# Power_Sergeant.net
KiCad netlist of a schematic drawn in Altium Designer
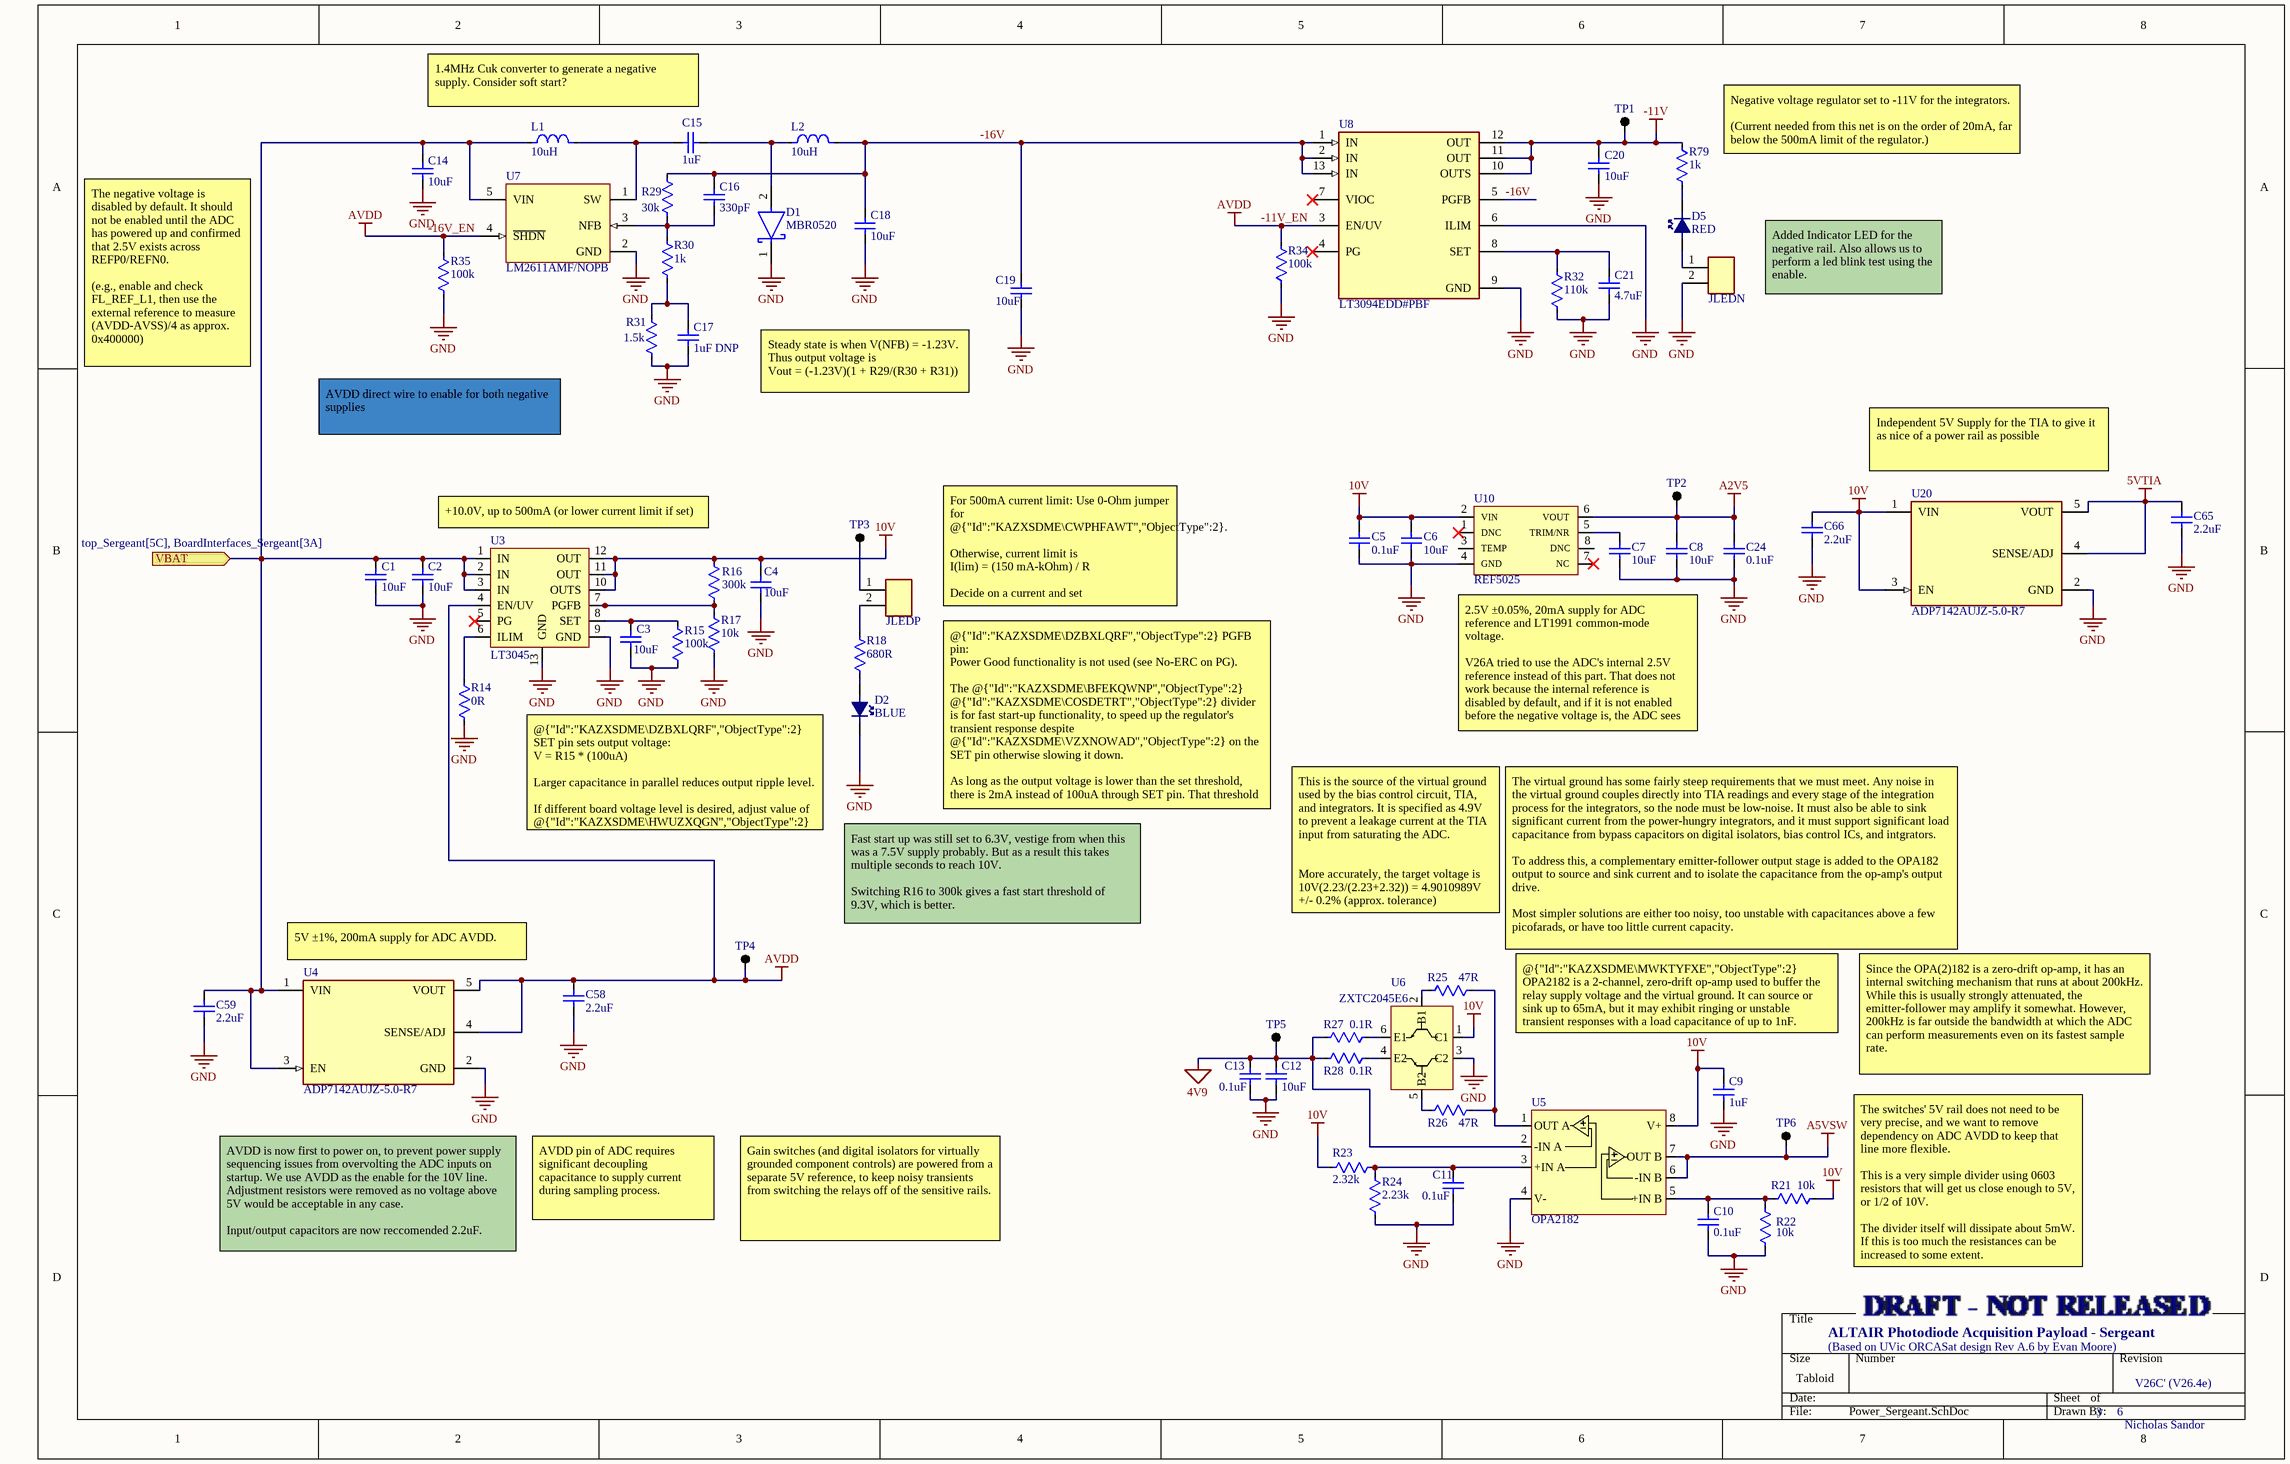
[diagram p0: Power_Sergeant.SchDoc]

(export (version "E")
  (design (tool "Eeschema 10.0.6"))
  (components
    (comp (ref "C1")
      (value "10uF")
      (footprint "CAP 1206 IPC LOW DENSITY")
      (description "Murata GRT319R6YA106KE01D - Cap Ceramic 10uF 35V X5R 10% Pad SMD 1206 85C Automotive T/R")
      (fields (field (name "MF") "Murata") (field (name "MP") "GRT319R6YA106KE01D"))
      (libsource (lib "ALTAIR_PD_Capacitors") (part "CAP"))
    )
    (comp (ref "C2")
      (value "10uF")
      (footprint "CAP 1206 IPC LOW DENSITY")
      (description "Murata GRT319R6YA106KE01D - Cap Ceramic 10uF 35V X5R 10% Pad SMD 1206 85C Automotive T/R")
      (fields (field (name "MF") "Murata") (field (name "MP") "GRT319R6YA106KE01D"))
      (libsource (lib "ALTAIR_PD_Capacitors") (part "CAP"))
    )
    (comp (ref "C3")
      (value "10uF")
      (footprint "CAP 1206 IPC LOW DENSITY")
      (description "Murata GRT319R6YA106KE01D - Cap Ceramic 10uF 35V X5R 10% Pad SMD 1206 85C Automotive T/R")
      (fields (field (name "MF") "Murata") (field (name "MP") "GRT319R6YA106KE01D"))
      (libsource (lib "ALTAIR_PD_Capacitors") (part "CAP"))
    )
    (comp (ref "C4")
      (value "10uF")
      (footprint "CAP 1206 IPC LOW DENSITY")
      (description "Murata GRT319R6YA106KE01D - Cap Ceramic 10uF 35V X5R 10% Pad SMD 1206 85C Automotive T/R")
      (fields (field (name "MF") "Murata") (field (name "MP") "GRT319R6YA106KE01D"))
      (libsource (lib "ALTAIR_PD_Capacitors") (part "CAP"))
    )
    (comp (ref "C5")
      (value "0.1uF")
      (footprint "CAP 0603 IPC MID DENSITY")
      (description "Kemet C0603C104K5RACAUTO - Cap Ceramic 0.1uF 50V X7R 10% 0603 125C Paper T/R")
      (fields (field (name "MF") "Kemet") (field (name "MP") "C0603C104K5RACAUTO"))
      (libsource (lib "ALTAIR_PD_Capacitors") (part "CAP"))
    )
    (comp (ref "C6")
      (value "10uF")
      (footprint "CAP 0805 IPC MID DENSITY")
      (description "Murata GRM21BR61E106KA73L - Cap Ceramic 10uF 10% 25V X5R 0805")
      (fields (field (name "MF") "Murata") (field (name "MP") "GRM21BR61E106KA73L"))
      (libsource (lib "ALTAIR_PD_Capacitors") (part "CAP"))
    )
    (comp (ref "C7")
      (value "10uF")
      (footprint "CAP 0805 IPC MID DENSITY")
      (description "Murata GRM21BR61E106KA73L - Cap Ceramic 10uF 10% 25V X5R 0805")
      (fields (field (name "MF") "Murata") (field (name "MP") "GRM21BR61E106KA73L"))
      (libsource (lib "ALTAIR_PD_Capacitors") (part "CAP"))
    )
    (comp (ref "C8")
      (value "10uF")
      (footprint "CAP 0805 IPC MID DENSITY")
      (description "Murata GRM21BR61E106KA73L - Cap Ceramic 10uF 10% 25V X5R 0805")
      (fields (field (name "MF") "Murata") (field (name "MP") "GRM21BR61E106KA73L"))
      (libsource (lib "ALTAIR_PD_Capacitors") (part "CAP"))
    )
    (comp (ref "C9")
      (value "1uF")
      (footprint "CAP 0603 IPC MID DENSITY")
      (description "Murata GRT188R61H105KE13D - Cap MLCC AEC-Q200 X5R 1uF 50V 0603")
      (fields (field (name "MF") "Murata") (field (name "MP") "GRT188R61H105KE13D"))
      (libsource (lib "ALTAIR_PD_Capacitors") (part "CAP"))
    )
    (comp (ref "C10")
      (value "0.1uF")
      (footprint "CAP 0603 IPC MID DENSITY")
      (description "Kemet C0603C104K5RACAUTO - Cap Ceramic 0.1uF 50V X7R 10% 0603 125C Paper T/R")
      (fields (field (name "MF") "Kemet") (field (name "MP") "C0603C104K5RACAUTO"))
      (libsource (lib "ALTAIR_PD_Capacitors") (part "CAP"))
    )
    (comp (ref "C11")
      (value "0.1uF")
      (footprint "CAP 0603 IPC MID DENSITY")
      (description "Kemet C0603C104K5RACAUTO - Cap Ceramic 0.1uF 50V X7R 10% 0603 125C Paper T/R")
      (fields (field (name "MF") "Kemet") (field (name "MP") "C0603C104K5RACAUTO"))
      (libsource (lib "ALTAIR_PD_Capacitors") (part "CAP"))
    )
    (comp (ref "C12")
      (value "10uF")
      (footprint "CAP 1206 IPC LOW DENSITY")
      (description "Murata GRT319R6YA106KE01D - Cap Ceramic 10uF 35V X5R 10% Pad SMD 1206 85C Automotive T/R")
      (fields (field (name "MF") "Murata") (field (name "MP") "GRT319R6YA106KE01D"))
      (libsource (lib "ALTAIR_PD_Capacitors") (part "CAP"))
    )
    (comp (ref "C13")
      (value "0.1uF")
      (footprint "CAP 0603 IPC MID DENSITY")
      (description "Kemet C0603C104K5RACAUTO - Cap Ceramic 0.1uF 50V X7R 10% 0603 125C Paper T/R")
      (fields (field (name "MF") "Kemet") (field (name "MP") "C0603C104K5RACAUTO"))
      (libsource (lib "ALTAIR_PD_Capacitors") (part "CAP"))
    )
    (comp (ref "C14")
      (value "10uF")
      (footprint "CAP 0805 IPC MID DENSITY")
      (description "Murata GRM21BR61E106KA73L - Cap Ceramic 10uF 10% 25V X5R 0805")
      (fields (field (name "MF") "Murata") (field (name "MP") "GRM21BR61E106KA73L"))
      (libsource (lib "ALTAIR_PD_Capacitors") (part "CAP"))
    )
    (comp (ref "C15")
      (value "1uF")
      (footprint "CAP 0603 IPC MID DENSITY")
      (description "Murata GRT188R61H105KE13D - Cap MLCC AEC-Q200 X5R 1uF 50V 0603")
      (fields (field (name "MF") "Murata") (field (name "MP") "GRT188R61H105KE13D"))
      (libsource (lib "ALTAIR_PD_Capacitors") (part "CAP"))
    )
    (comp (ref "C16")
      (value "330pF")
      (footprint "CAP 1206 NON-IPC KEMET NP0")
      (description "Kemet C1206C331J5GACTU - Cap Ceramic 330pF 50V 5% NP0 1206")
      (fields (field (name "MF") "Kemet") (field (name "MP") "C1206C331J5GACTU"))
      (libsource (lib "ALTAIR_PD_Capacitors") (part "CAP"))
    )
    (comp (ref "C17")
      (value "1uF DNP")
      (footprint "CAP 0603 IPC MID DENSITY")
      (description "Murata GRT188R61H105KE13D - Cap MLCC AEC-Q200 X5R 1uF 50V 0603")
      (fields (field (name "MF") "Murata") (field (name "MP") "GRT188R61H105KE13D"))
      (libsource (lib "ALTAIR_PD_Capacitors") (part "CAP"))
    )
    (comp (ref "C18")
      (value "10uF")
      (footprint "CAP 0805 IPC MID DENSITY")
      (description "Murata GRM21BR61E106KA73L - Cap Ceramic 10uF 10% 25V X5R 0805")
      (fields (field (name "MF") "Murata") (field (name "MP") "GRM21BR61E106KA73L"))
      (libsource (lib "ALTAIR_PD_Capacitors") (part "CAP"))
    )
    (comp (ref "C19")
      (value "10uF")
      (footprint "CAP 0805 IPC MID DENSITY")
      (description "Murata GRM21BR61E106KA73L - Cap Ceramic 10uF 10% 25V X5R 0805")
      (fields (field (name "MF") "Murata") (field (name "MP") "GRM21BR61E106KA73L"))
      (libsource (lib "ALTAIR_PD_Capacitors") (part "CAP"))
    )
    (comp (ref "C20")
      (value "10uF")
      (footprint "CAP 0805 IPC MID DENSITY")
      (description "Murata GRM21BR61E106KA73L - Cap Ceramic 10uF 10% 25V X5R 0805")
      (fields (field (name "MF") "Murata") (field (name "MP") "GRM21BR61E106KA73L"))
      (libsource (lib "ALTAIR_PD_Capacitors") (part "CAP"))
    )
    (comp (ref "C21")
      (value "4.7uF")
      (footprint "CAP 0805 NON-IPC KEMET X5R")
      (description "Kemet C0805C475K8PACTU - Cap Ceramic 4.7uF 10V X5R 0805")
      (fields (field (name "MF") "Kemet") (field (name "MP") "C0805C475K8PACTU"))
      (libsource (lib "ALTAIR_PD_Capacitors") (part "CAP"))
    )
    (comp (ref "C24")
      (value "0.1uF")
      (footprint "CAP 0603 IPC MID DENSITY")
      (description "Kemet C0603C104K5RACAUTO - Cap Ceramic 0.1uF 50V X7R 10% 0603 125C Paper T/R")
      (fields (field (name "MF") "Kemet") (field (name "MP") "C0603C104K5RACAUTO"))
      (libsource (lib "ALTAIR_PD_Capacitors") (part "CAP"))
    )
    (comp (ref "C58")
      (value "2.2uF")
      (footprint "CAP 1206 UNKNOWN")
      (description "CL31B225KBHNNNE CAP CER 2.2UF 50V X7R 1206")
      (fields (field (name "MF") "Samsung Electro-Mechanics") (field (name "MP") "CL31B225KBHNNNE"))
      (libsource (lib "ALTAIR_PD_Capacitors") (part "CAP"))
    )
    (comp (ref "C59")
      (value "2.2uF")
      (footprint "CAP 1206 UNKNOWN")
      (description "CL31B225KBHNNNE CAP CER 2.2UF 50V X7R 1206")
      (fields (field (name "MF") "Samsung Electro-Mechanics") (field (name "MP") "CL31B225KBHNNNE"))
      (libsource (lib "ALTAIR_PD_Capacitors") (part "CAP"))
    )
    (comp (ref "C65")
      (value "2.2uF")
      (footprint "CAP 1206 UNKNOWN")
      (description "CL31B225KBHNNNE CAP CER 2.2UF 50V X7R 1206")
      (fields (field (name "MF") "Samsung Electro-Mechanics") (field (name "MP") "CL31B225KBHNNNE"))
      (libsource (lib "ALTAIR_PD_Capacitors") (part "CAP"))
    )
    (comp (ref "C66")
      (value "2.2uF")
      (footprint "CAP 1206 UNKNOWN")
      (description "CL31B225KBHNNNE CAP CER 2.2UF 50V X7R 1206")
      (fields (field (name "MF") "Samsung Electro-Mechanics") (field (name "MP") "CL31B225KBHNNNE"))
      (libsource (lib "ALTAIR_PD_Capacitors") (part "CAP"))
    )
    (comp (ref "D1")
      (value "MBR0520")
      (footprint "SOD-123 ONSEMI SMALL PADS")
      (description "DIODE SCHOTTKY 20V 500MA SOD123")
      (fields (field (name "MF") "onsemi") (field (name "MP") "MBR0520LT1G"))
      (libsource (lib "ALTAIR_PD_Diodes") (part "Schottky"))
    )
    (comp (ref "D2")
      (value "BLUE")
      (footprint "LED 0603 MID DENSITY")
      (description "LED BLUE CLEAR 0603 SMD")
      (fields (field (name "MF") "Wurth Electronics") (field (name "MP") "150060BS75000"))
      (libsource (lib "ALTAIR_PD_Diodes") (part "LED-blue"))
    )
    (comp (ref "D5")
      (value "RED")
      (footprint "LED 0603 MID DENSITY")
      (description "LED RED CLEAR 0603 SMD")
      (fields (field (name "MF") "Wurth Electronics") (field (name "MP") "150060RS75000"))
      (libsource (lib "ALTAIR_PD_Diodes") (part "LED-blue"))
    )
    (comp (ref "JLEDN")
      (value "JLED")
      (footprint "JUMPER 2POS 1MM PITCH THT")
      (description "2x1 Header THT 1mm Pitch")
      (fields
        (field (name "MF") "GCT (GLOBAL CONNECTOR TECHNOLOGY)")
        (field (name "MP") "BC020-02-A-0200-0300-L-G")
      )
      (libsource (lib "ALTAIR_PD_Headers") (part "BC020-02-A-0200-0300-L-G"))
    )
    (comp (ref "JLEDP")
      (value "JLED")
      (footprint "ALTAIR_PD_Headers:JUMPER 2POS 1MM PITCH THT")
      (description "2x1 Header THT 1mm Pitch")
      (fields
        (field (name "MF") "GCT (GLOBAL CONNECTOR TECHNOLOGY)")
        (field (name "MP") "BC020-02-A-0200-0300-L-G")
      )
      (libsource (lib "ALTAIR_PD_Headers") (part "BC020-02-A-0200-0300-L-G"))
    )
    (comp (ref "L1")
      (value "10uH")
      (footprint "IND VLS3012CX-1 NONSTANDARD TDK")
      (description "TDK VLS3012CX-100M-1 - Inductor 10uH 20% 1.25A 0.324Ohm NonstandardPkg")
      (fields (field (name "TOLERANCE") "20%") (field (name "MF") "TDK Corporation"))
      (libsource (lib "ALTAIR_PD_Inductors") (part "IND"))
    )
    (comp (ref "L2")
      (value "10uH")
      (footprint "IND VLS3012CX-1 NONSTANDARD TDK")
      (description "TDK VLS3012CX-100M-1 - Inductor 10uH 20% 1.25A 0.324Ohm NonstandardPkg")
      (fields (field (name "TOLERANCE") "20%") (field (name "MF") "TDK Corporation"))
      (libsource (lib "ALTAIR_PD_Inductors") (part "IND"))
    )
    (comp (ref "R14")
      (value "0R")
      (footprint "RES 0603 IPC MID DENSITY")
      (description "Vishay CRCW06030000Z0EA - Res 0 Ohms 1/8W SMD 0603")
      (fields (field (name "MF") "Vishay Dale") (field (name "MP") "CRCW06030000Z0EA"))
      (libsource (lib "ALTAIR_PD_Resistors") (part "RES"))
    )
    (comp (ref "R15")
      (value "100k")
      (footprint "RES 0603 IPC MID DENSITY")
      (description "Panasonic ERA-3ARB104V - Res SMD 0603 0.1% 0.10W T.C. 10ppm 100K")
      (fields (field (name "MF") "Panasonic Electronic Components") (field (name "MP") "ERA-3ARB104V"))
      (libsource (lib "ALTAIR_PD_Resistors") (part "RES"))
    )
    (comp (ref "R16")
      (value "300k")
      (footprint "RES 0603 IPC MID DENSITY")
      (description "Vishay MCT06030C3003FP500 - Res SMD 300kOhm 1% 1/10W 0603")
      (fields (field (name "MF") "Vishay Dale") (field (name "MP") "MCT06030C3003FP500"))
      (libsource (lib "ALTAIR_PD_Resistors") (part "RES"))
    )
    (comp (ref "R17")
      (value "10k")
      (footprint "RES 0603 IPC MID DENSITY")
      (description "Vishay CRCW060310K0FKEA SMD 0603 10k, CRCW e3 Series, 75V, thick film, 100mW")
      (fields (field (name "MF") "Vishay Dale") (field (name "MP") "CRCW060310K0FKEA"))
      (libsource (lib "ALTAIR_PD_Resistors") (part "RES"))
    )
    (comp (ref "R18")
      (value "680R")
      (footprint "RES 0603 IPC MID DENSITY")
      (description "Panasonic ERJ-3EKF6800V - Res SMD 680 Ohm 1% 1/10W 0603")
      (fields (field (name "MF") "Panasonic Electronic Components") (field (name "MP") "ERJ-3EKF6800V"))
      (libsource (lib "ALTAIR_PD_Resistors") (part "RES"))
    )
    (comp (ref "R21")
      (value "10k")
      (footprint "RES 0603 IPC MID DENSITY")
      (description "Vishay CRCW060310K0FKEA SMD 0603 10k, CRCW e3 Series, 75V, thick film, 100mW")
      (fields (field (name "MF") "Vishay Dale") (field (name "MP") "CRCW060310K0FKEA"))
      (libsource (lib "ALTAIR_PD_Resistors") (part "RES"))
    )
    (comp (ref "R22")
      (value "10k")
      (footprint "RES 0603 IPC MID DENSITY")
      (description "Vishay CRCW060310K0FKEA SMD 0603 10k, CRCW e3 Series, 75V, thick film, 100mW")
      (fields (field (name "MF") "Vishay Dale") (field (name "MP") "CRCW060310K0FKEA"))
      (libsource (lib "ALTAIR_PD_Resistors") (part "RES"))
    )
    (comp (ref "R23")
      (value "2.32k")
      (footprint "RES 0603 IPC MID DENSITY")
      (description "Vishay TNPW06032K32BEEA - Res 2.32k 0.1% 0.21W SMD 0603")
      (fields (field (name "MF") "Vishay Dale") (field (name "MP") "TNPW06032K32BEEA"))
      (libsource (lib "ALTAIR_PD_Resistors") (part "RES"))
    )
    (comp (ref "R24")
      (value "2.23k")
      (footprint "RES 0603 IPC MID DENSITY")
      (description "KOA Speer RN73R1JTTD2231B25 - Res 2.23k 0.1% 1/10W SMD 0603")
      (fields (field (name "MF") "KOA Speer Electronics, Inc.") (field (name "MP") "RN73R1JTTD2231B25"))
      (libsource (lib "ALTAIR_PD_Resistors") (part "RES"))
    )
    (comp (ref "R25")
      (value "47R")
      (footprint "RES 0402 NON-IPC SEI")
      (description "Stackpole RMCF0402JT47R0 - Res 47Ohm 5% 0.063W 0402 Thick Film AEC-Q200 compliant")
      (fields (field (name "MF") "Stackpole Electronics Inc.") (field (name "MP") "RMCF0402JT47R0"))
      (libsource (lib "ALTAIR_PD_Resistors") (part "RES"))
    )
    (comp (ref "R26")
      (value "47R")
      (footprint "RES 0402 NON-IPC SEI")
      (description "Stackpole RMCF0402JT47R0 - Res 47Ohm 5% 0.063W 0402 Thick Film AEC-Q200 compliant")
      (fields (field (name "MF") "Stackpole Electronics Inc.") (field (name "MP") "RMCF0402JT47R0"))
      (libsource (lib "ALTAIR_PD_Resistors") (part "RES"))
    )
    (comp (ref "R27")
      (value "0.1R")
      (footprint "RES 0402 NON-IPC YAGEO")
      (description "Yageo RL0402JR-070R1L - Res 0.1Ohm 5% 1/16W SMD 0402")
      (fields (field (name "MF") "YAGEO") (field (name "MP") "RL0402JR-070R1L"))
      (libsource (lib "ALTAIR_PD_Resistors") (part "RES"))
    )
    (comp (ref "R28")
      (value "0.1R")
      (footprint "RES 0402 NON-IPC YAGEO")
      (description "Yageo RL0402JR-070R1L - Res 0.1Ohm 5% 1/16W SMD 0402")
      (fields (field (name "MF") "YAGEO") (field (name "MP") "RL0402JR-070R1L"))
      (libsource (lib "ALTAIR_PD_Resistors") (part "RES"))
    )
    (comp (ref "R29")
      (value "30k")
      (footprint "RES 0805 IPC HIGH DENSITY")
      (description "Panasonic ERA-6AEB303V - Res 30kOhm 0.1% 1/8W 0805")
      (fields (field (name "MF") "Panasonic Electronic Components") (field (name "MP") "ERA-6AEB303V"))
      (libsource (lib "ALTAIR_PD_Resistors") (part "RES"))
    )
    (comp (ref "R30")
      (value "1k")
      (footprint "RES 0402 IPC LOW DENSITY YAGEO")
      (description "Yageo RC0402FR-071KL - Res 1kOhm 1% 1/16W 0402")
      (fields (field (name "MF") "YAGEO") (field (name "MP") "RC0402FR-071KL"))
      (libsource (lib "ALTAIR_PD_Resistors") (part "RES"))
    )
    (comp (ref "R31")
      (value "1.5k")
      (footprint "RES 1206 NON-IPC VISHAY")
      (description "Vishay TNPU12061K50BZEN00 - Res 1.5kOhm 0.1% 1/4W 1206")
      (fields (field (name "MF") "Vishay Dale") (field (name "MP") "TNPU12061K50BZEN00"))
      (libsource (lib "ALTAIR_PD_Resistors") (part "RES"))
    )
    (comp (ref "R32")
      (value "110k")
      (footprint "RES 0603 IPC MID DENSITY")
      (description "Panasonic ERA-3AEB114V - Res 110k 0.1% 1/10W SMD 0603")
      (fields (field (name "MF") "Panasonic Electronic Components") (field (name "MP") "ERA-3AEB114V"))
      (libsource (lib "ALTAIR_PD_Resistors") (part "RES"))
    )
    (comp (ref "R34")
      (value "100k")
      (footprint "RES 0603 IPC MID DENSITY")
      (description "Panasonic ERJ-3GEYJ104V - Res 100k 5% 1/10W SMD 0603")
      (fields (field (name "MF") "Panasonic Electronic Components") (field (name "MP") "ERJ-3GEYJ104V"))
      (libsource (lib "ALTAIR_PD_Resistors") (part "RES"))
    )
    (comp (ref "R35")
      (value "100k")
      (footprint "RES 0603 IPC MID DENSITY")
      (description "Panasonic ERJ-3GEYJ104V - Res 100k 5% 1/10W SMD 0603")
      (fields (field (name "MF") "Panasonic Electronic Components") (field (name "MP") "ERJ-3GEYJ104V"))
      (libsource (lib "ALTAIR_PD_Resistors") (part "RES"))
    )
    (comp (ref "R79")
      (value "1k")
      (footprint "RES 0603 IPC MID DENSITY")
      (description "Panasonic ERJ-U03F1001V - Res SMD 1 kOhm 1% 1/10W 0603")
      (fields (field (name "MF") "Panasonic Electronic Components") (field (name "MP") "ERJ-U03F1001V"))
      (libsource (lib "ALTAIR_PD_Resistors") (part "RES"))
    )
    (comp (ref "TP1")
      (value "Testpoint")
      (footprint "TESTPOINT THT")
      (libsource (lib "ALTAIR_PD_Testpoint") (part "Testpoint"))
    )
    (comp (ref "TP2")
      (value "Testpoint")
      (footprint "TESTPOINT THT")
      (libsource (lib "ALTAIR_PD_Testpoint") (part "Testpoint"))
    )
    (comp (ref "TP3")
      (value "Testpoint")
      (footprint "TESTPOINT THT")
      (libsource (lib "ALTAIR_PD_Testpoint") (part "Testpoint"))
    )
    (comp (ref "TP4")
      (value "Testpoint")
      (footprint "TESTPOINT THT")
      (libsource (lib "ALTAIR_PD_Testpoint") (part "Testpoint"))
    )
    (comp (ref "TP5")
      (value "Testpoint")
      (footprint "TESTPOINT THT")
      (libsource (lib "ALTAIR_PD_Testpoint") (part "Testpoint"))
    )
    (comp (ref "TP6")
      (value "Testpoint")
      (footprint "TESTPOINT THT")
      (libsource (lib "ALTAIR_PD_Testpoint") (part "Testpoint"))
    )
    (comp (ref "U3")
      (value "LT3045")
      (footprint "12-TSOP 0.65MM PITCH 3MM WIDTH EP IPC MID DENSITY")
      (description "20V 500mA Ultralow Noise Ultrahigh PSRR Adjustable Linear Regulator 260V Dropout MSOP-12")
      (fields (field (name "MF") "Analog Devices / Linear Technology") (field (name "MP") "LT3045EMSE#PBF"))
      (libsource (lib "ALTAIR_PD_Regulators") (part "LT3045"))
    )
    (comp (ref "U4")
      (value "ADP7142AUJZ-5.0-R7")
      (footprint "SOT23-5 HIGH DENSITY AD")
      (description "1.2-40V 200mA Low Noise CMOS LDO Adjustable Linear Regulator TSOT23")
      (fields
        (field (name "OCTOPART") "https://octopart.com/adp7142aujz-r7-analog+devices-38928114")
        (field (name "MF") "Analog Devices")
      )
      (libsource (lib "ALTAIR_PD_Regulators") (part "ADP7142AUJZ-R7"))
    )
    (comp (ref "U5")
      (value "OPA2182")
      (footprint "8-TSSOP 0.65MM PITCH 4.4MM WIDTH IPC MID DENSITY")
      (fields (field (name "MF") "Texas Instruments") (field (name "MP") "OPA2182IDGKR"))
      (libsource (lib "ALTAIR_PD_Amplifiers") (part "OPA2182IDBV"))
    )
    (comp (ref "U6")
      (value "ZXTC2045E6")
      (footprint "SOT23-6 NON-IPC DIODES")
      (description "BJT Array, 1NPN 1PNP, VCE(sat) 375mV, hFE 300, Breakdown 30V, 6-SOT-23")
      (fields (field (name "MF") "Diodes Incorporated") (field (name "MP") "ZXTC2045E6TA"))
      (libsource (lib "ALTAIR_PD_BJTs") (part "ZXTC2045E6"))
    )
    (comp (ref "U7")
      (value "LM2611AMF/NOPB")
      (footprint "SOT23-5 MID DENSITY")
      (description "1.4MHz Cuk Converter, 5-pin SOT-23, Pb-Free")
      (fields (field (name "MF") "Texas Instruments"))
      (libsource (lib "ALTAIR_PD_Converters") (part "LM2611AMF"))
    )
    (comp (ref "U8")
      (value "LT3094EDD#PBF")
      (footprint "12DFN 3x3MM EP IPC MID DENSITY")
      (description "-20V 500mA Ultralow Noise Ultrahigh PSRR Adjustable Negative Linear Regulator 12DFN")
      (fields (field (name "MF") "Analog Devices"))
      (libsource (lib "ALTAIR_PD_Regulators") (part "LT3094EDD#PBF"))
    )
    (comp (ref "U10")
      (value "REF5025")
      (footprint "8-TSOP 0.65MM PITCH 3MM WIDTH IPC MID DENSITY")
      (description "2.5V±0.05% Voltage Reference 8VSSOP")
      (fields (field (name "MF") "Texas Instruments") (field (name "MP") "REF5025IDGKR"))
      (libsource (lib "ALTAIR_PD_MiscPower") (part "REF5050IDGKR"))
    )
    (comp (ref "U20")
      (value "ADP7142AUJZ-5.0-R7")
      (footprint "SOT23-5 HIGH DENSITY AD")
      (description "1.2-40V 200mA Low Noise CMOS LDO Adjustable Linear Regulator TSOT23")
      (fields
        (field (name "OCTOPART") "https://octopart.com/adp7142aujz-r7-analog+devices-38928114")
        (field (name "MF") "Analog Devices")
      )
      (libsource (lib "ALTAIR_PD_Regulators") (part "ADP7142AUJZ-R7"))
    )
  )
  (nets
    (net (code "1") (name "-11V") (class "Default")
      (node (ref "C20") (pin "1") (pinfunction "1_1") (pintype "passive"))
      (node (ref "R79") (pin "2") (pinfunction "2_2") (pintype "passive"))
      (node (ref "TP1") (pin "1") (pinfunction "1_1") (pintype "passive"))
      (node (ref "U8") (pin "10") (pinfunction "OUTS_10") (pintype "power_in"))
      (node (ref "U8") (pin "11") (pinfunction "OUT_11") (pintype "power_in"))
      (node (ref "U8") (pin "12") (pinfunction "OUT_12") (pintype "power_in"))
    )
    (net (code "2") (name "/-16V") (class "Default")
      (node (ref "C16") (pin "1") (pinfunction "1_1") (pintype "passive"))
      (node (ref "C18") (pin "1") (pinfunction "1_1") (pintype "passive"))
      (node (ref "C19") (pin "1") (pinfunction "1_1") (pintype "passive"))
      (node (ref "L2") (pin "2") (pinfunction "2_2") (pintype "passive"))
      (node (ref "R29") (pin "2") (pinfunction "2_2") (pintype "passive"))
      (node (ref "U8") (pin "1") (pinfunction "IN_1") (pintype "input"))
      (node (ref "U8") (pin "13") (pinfunction "IN_13") (pintype "input"))
      (node (ref "U8") (pin "2") (pinfunction "IN_2") (pintype "input"))
      (node (ref "U8") (pin "5") (pinfunction "PGFB_5") (pintype "passive"))
    )
    (net (code "3") (name "/VBAT") (class "Default")
      (node (ref "C1") (pin "2") (pinfunction "2_2") (pintype "passive"))
      (node (ref "C14") (pin "2") (pinfunction "2_2") (pintype "passive"))
      (node (ref "C2") (pin "2") (pinfunction "2_2") (pintype "passive"))
      (node (ref "C59") (pin "1") (pinfunction "1_1") (pintype "passive"))
      (node (ref "L1") (pin "1") (pinfunction "1_1") (pintype "passive"))
      (node (ref "U3") (pin "1") (pinfunction "IN_1") (pintype "passive"))
      (node (ref "U3") (pin "2") (pinfunction "IN_2") (pintype "passive"))
      (node (ref "U3") (pin "3") (pinfunction "IN_3") (pintype "passive"))
      (node (ref "U4") (pin "1") (pinfunction "VIN_1") (pintype "power_in"))
      (node (ref "U4") (pin "3") (pinfunction "EN_3") (pintype "input"))
      (node (ref "U7") (pin "5") (pinfunction "VIN_5") (pintype "power_in"))
    )
    (net (code "4") (name "4V9") (class "Default")
      (node (ref "C12") (pin "2") (pinfunction "2_2") (pintype "passive"))
      (node (ref "C13") (pin "2") (pinfunction "2_2") (pintype "passive"))
      (node (ref "R27") (pin "1") (pinfunction "1_1") (pintype "passive"))
      (node (ref "R28") (pin "1") (pinfunction "1_1") (pintype "passive"))
      (node (ref "TP5") (pin "1") (pinfunction "1_1") (pintype "passive"))
      (node (ref "U5") (pin "2") (pinfunction "-IN_A_2") (pintype "passive"))
    )
    (net (code "5") (name "5VTIA") (class "Default")
      (node (ref "C65") (pin "1") (pinfunction "1_1") (pintype "passive"))
      (node (ref "U20") (pin "4") (pinfunction "SENSE/ADJ_4") (pintype "passive"))
      (node (ref "U20") (pin "5") (pinfunction "VOUT_5") (pintype "passive"))
    )
    (net (code "6") (name "10V") (class "Default")
      (node (ref "C4") (pin "2") (pinfunction "2_2") (pintype "passive"))
      (node (ref "C5") (pin "1") (pinfunction "1_1") (pintype "passive"))
      (node (ref "C6") (pin "2") (pinfunction "2_2") (pintype "passive"))
      (node (ref "C66") (pin "1") (pinfunction "1_1") (pintype "passive"))
      (node (ref "C9") (pin "2") (pinfunction "2_2") (pintype "passive"))
      (node (ref "JLEDP") (pin "1") (pinfunction "1_1") (pintype "passive"))
      (node (ref "R16") (pin "2") (pinfunction "2_2") (pintype "passive"))
      (node (ref "R21") (pin "2") (pinfunction "2_2") (pintype "passive"))
      (node (ref "R23") (pin "2") (pinfunction "2_2") (pintype "passive"))
      (node (ref "TP3") (pin "1") (pinfunction "1_1") (pintype "passive"))
      (node (ref "U10") (pin "2") (pinfunction "VIN_2") (pintype "passive"))
      (node (ref "U20") (pin "1") (pinfunction "VIN_1") (pintype "power_in"))
      (node (ref "U20") (pin "3") (pinfunction "EN_3") (pintype "input"))
      (node (ref "U3") (pin "10") (pinfunction "OUTS_10") (pintype "passive"))
      (node (ref "U3") (pin "11") (pinfunction "OUT_11") (pintype "passive"))
      (node (ref "U3") (pin "12") (pinfunction "OUT_12") (pintype "passive"))
      (node (ref "U5") (pin "8") (pinfunction "V+_8") (pintype "passive"))
      (node (ref "U6") (pin "1") (pinfunction "C1_1") (pintype "passive"))
    )
    (net (code "7") (name "A2V5") (class "Default")
      (node (ref "C24") (pin "1") (pinfunction "1_1") (pintype "passive"))
      (node (ref "C8") (pin "2") (pinfunction "2_2") (pintype "passive"))
      (node (ref "TP2") (pin "1") (pinfunction "1_1") (pintype "passive"))
      (node (ref "U10") (pin "6") (pinfunction "VOUT_6") (pintype "passive"))
    )
    (net (code "8") (name "A5VSW") (class "Default")
      (node (ref "TP6") (pin "1") (pinfunction "1_1") (pintype "passive"))
      (node (ref "U5") (pin "6") (pinfunction "-IN_B_6") (pintype "passive"))
      (node (ref "U5") (pin "7") (pinfunction "OUT_B_7") (pintype "passive"))
    )
    (net (code "9") (name "AVDD") (class "Default")
      (node (ref "C58") (pin "1") (pinfunction "1_1") (pintype "passive"))
      (node (ref "R34") (pin "1") (pinfunction "1_1") (pintype "passive"))
      (node (ref "R35") (pin "1") (pinfunction "1_1") (pintype "passive"))
      (node (ref "TP4") (pin "1") (pinfunction "1_1") (pintype "passive"))
      (node (ref "U3") (pin "4") (pinfunction "EN/UV_4") (pintype "passive"))
      (node (ref "U4") (pin "4") (pinfunction "SENSE/ADJ_4") (pintype "passive"))
      (node (ref "U4") (pin "5") (pinfunction "VOUT_5") (pintype "passive"))
      (node (ref "U7") (pin "4") (pinfunction "~{SHDN}_4") (pintype "input"))
      (node (ref "U8") (pin "3") (pinfunction "EN/UV_3") (pintype "passive"))
    )
    (net (code "10") (name "GND") (class "Default")
      (node (ref "C1") (pin "1") (pinfunction "1_1") (pintype "passive"))
      (node (ref "C10") (pin "1") (pinfunction "1_1") (pintype "passive"))
      (node (ref "C11") (pin "1") (pinfunction "1_1") (pintype "passive"))
      (node (ref "C12") (pin "1") (pinfunction "1_1") (pintype "passive"))
      (node (ref "C13") (pin "1") (pinfunction "1_1") (pintype "passive"))
      (node (ref "C14") (pin "1") (pinfunction "1_1") (pintype "passive"))
      (node (ref "C17") (pin "2") (pinfunction "2_2") (pintype "passive"))
      (node (ref "C18") (pin "2") (pinfunction "2_2") (pintype "passive"))
      (node (ref "C19") (pin "2") (pinfunction "2_2") (pintype "passive"))
      (node (ref "C2") (pin "1") (pinfunction "1_1") (pintype "passive"))
      (node (ref "C20") (pin "2") (pinfunction "2_2") (pintype "passive"))
      (node (ref "C21") (pin "2") (pinfunction "2_2") (pintype "passive"))
      (node (ref "C24") (pin "2") (pinfunction "2_2") (pintype "passive"))
      (node (ref "C3") (pin "1") (pinfunction "1_1") (pintype "passive"))
      (node (ref "C4") (pin "1") (pinfunction "1_1") (pintype "passive"))
      (node (ref "C5") (pin "2") (pinfunction "2_2") (pintype "passive"))
      (node (ref "C58") (pin "2") (pinfunction "2_2") (pintype "passive"))
      (node (ref "C59") (pin "2") (pinfunction "2_2") (pintype "passive"))
      (node (ref "C6") (pin "1") (pinfunction "1_1") (pintype "passive"))
      (node (ref "C65") (pin "2") (pinfunction "2_2") (pintype "passive"))
      (node (ref "C66") (pin "2") (pinfunction "2_2") (pintype "passive"))
      (node (ref "C7") (pin "2") (pinfunction "2_2") (pintype "passive"))
      (node (ref "C8") (pin "1") (pinfunction "1_1") (pintype "passive"))
      (node (ref "C9") (pin "1") (pinfunction "1_1") (pintype "passive"))
      (node (ref "D1") (pin "1") (pinfunction "C_1") (pintype "passive"))
      (node (ref "D2") (pin "1") (pinfunction "1_1") (pintype "passive"))
      (node (ref "JLEDN") (pin "2") (pinfunction "2_2") (pintype "passive"))
      (node (ref "R14") (pin "1") (pinfunction "1_1") (pintype "passive"))
      (node (ref "R15") (pin "1") (pinfunction "1_1") (pintype "passive"))
      (node (ref "R17") (pin "1") (pinfunction "1_1") (pintype "passive"))
      (node (ref "R22") (pin "1") (pinfunction "1_1") (pintype "passive"))
      (node (ref "R24") (pin "1") (pinfunction "1_1") (pintype "passive"))
      (node (ref "R31") (pin "1") (pinfunction "1_1") (pintype "passive"))
      (node (ref "R32") (pin "2") (pinfunction "2_2") (pintype "passive"))
      (node (ref "R34") (pin "2") (pinfunction "2_2") (pintype "passive"))
      (node (ref "R35") (pin "2") (pinfunction "2_2") (pintype "passive"))
      (node (ref "U10") (pin "4") (pinfunction "GND_4") (pintype "passive"))
      (node (ref "U20") (pin "2") (pinfunction "GND_2") (pintype "power_in"))
      (node (ref "U3") (pin "13") (pinfunction "GND_13") (pintype "passive"))
      (node (ref "U3") (pin "9") (pinfunction "GND_9") (pintype "passive"))
      (node (ref "U4") (pin "2") (pinfunction "GND_2") (pintype "power_in"))
      (node (ref "U5") (pin "4") (pinfunction "V-_4") (pintype "passive"))
      (node (ref "U6") (pin "3") (pinfunction "C2_3") (pintype "passive"))
      (node (ref "U7") (pin "2") (pinfunction "GND_2") (pintype "power_in"))
      (node (ref "U8") (pin "6") (pinfunction "ILIM_6") (pintype "passive"))
      (node (ref "U8") (pin "9") (pinfunction "GND_9") (pintype "power_in"))
    )
    (net (code "11") (name "Net-(C17-Pad1)") (class "Default")
      (node (ref "C17") (pin "1") (pinfunction "1_1") (pintype "passive"))
      (node (ref "R30") (pin "1") (pinfunction "1_1") (pintype "passive"))
      (node (ref "R31") (pin "2") (pinfunction "2_2") (pintype "passive"))
    )
    (net (code "12") (name "Net-(D1-A)") (class "Default")
      (node (ref "C15") (pin "2") (pinfunction "2_2") (pintype "passive"))
      (node (ref "D1") (pin "2") (pinfunction "A_2") (pintype "passive"))
      (node (ref "L2") (pin "1") (pinfunction "1_1") (pintype "passive"))
    )
    (net (code "13") (name "Net-(D2-Pad2)") (class "Default")
      (node (ref "D2") (pin "2") (pinfunction "2_2") (pintype "passive"))
      (node (ref "R18") (pin "1") (pinfunction "1_1") (pintype "passive"))
    )
    (net (code "14") (name "Net-(D5-Pad1)") (class "Default")
      (node (ref "D5") (pin "1") (pinfunction "1_1") (pintype "passive"))
      (node (ref "R79") (pin "1") (pinfunction "1_1") (pintype "passive"))
    )
    (net (code "15") (name "Net-(D5-Pad2)") (class "Default")
      (node (ref "D5") (pin "2") (pinfunction "2_2") (pintype "passive"))
      (node (ref "JLEDN") (pin "1") (pinfunction "1_1") (pintype "passive"))
    )
    (net (code "16") (name "Net-(JLEDP-Pad2)") (class "Default")
      (node (ref "JLEDP") (pin "2") (pinfunction "2_2") (pintype "passive"))
      (node (ref "R18") (pin "2") (pinfunction "2_2") (pintype "passive"))
    )
    (net (code "17") (name "Net-(U3-ILIM)") (class "Default")
      (node (ref "R14") (pin "2") (pinfunction "2_2") (pintype "passive"))
      (node (ref "U3") (pin "6") (pinfunction "ILIM_6") (pintype "passive"))
    )
    (net (code "18") (name "Net-(U3-PGFB)") (class "Default")
      (node (ref "R16") (pin "1") (pinfunction "1_1") (pintype "passive"))
      (node (ref "R17") (pin "2") (pinfunction "2_2") (pintype "passive"))
      (node (ref "U3") (pin "7") (pinfunction "PGFB_7") (pintype "passive"))
    )
    (net (code "19") (name "Net-(U3-SET)") (class "Default")
      (node (ref "C3") (pin "2") (pinfunction "2_2") (pintype "passive"))
      (node (ref "R15") (pin "2") (pinfunction "2_2") (pintype "passive"))
      (node (ref "U3") (pin "8") (pinfunction "SET_8") (pintype "passive"))
    )
    (net (code "20") (name "Net-(U5-+IN_A)") (class "Default")
      (node (ref "C11") (pin "2") (pinfunction "2_2") (pintype "passive"))
      (node (ref "R23") (pin "1") (pinfunction "1_1") (pintype "passive"))
      (node (ref "R24") (pin "2") (pinfunction "2_2") (pintype "passive"))
      (node (ref "U5") (pin "3") (pinfunction "+IN_A_3") (pintype "passive"))
    )
    (net (code "21") (name "Net-(U5-+IN_B)") (class "Default")
      (node (ref "C10") (pin "2") (pinfunction "2_2") (pintype "passive"))
      (node (ref "R21") (pin "1") (pinfunction "1_1") (pintype "passive"))
      (node (ref "R22") (pin "2") (pinfunction "2_2") (pintype "passive"))
      (node (ref "U5") (pin "5") (pinfunction "+IN_B_5") (pintype "passive"))
    )
    (net (code "22") (name "Net-(U5-OUT_A)") (class "Default")
      (node (ref "R25") (pin "2") (pinfunction "2_2") (pintype "passive"))
      (node (ref "R26") (pin "2") (pinfunction "2_2") (pintype "passive"))
      (node (ref "U5") (pin "1") (pinfunction "OUT_A_1") (pintype "passive"))
    )
    (net (code "23") (name "Net-(U6-B1)") (class "Default")
      (node (ref "R25") (pin "1") (pinfunction "1_1") (pintype "passive"))
      (node (ref "U6") (pin "2") (pinfunction "B1_2") (pintype "passive"))
    )
    (net (code "24") (name "Net-(U6-B2)") (class "Default")
      (node (ref "R26") (pin "1") (pinfunction "1_1") (pintype "passive"))
      (node (ref "U6") (pin "5") (pinfunction "B2_5") (pintype "passive"))
    )
    (net (code "25") (name "Net-(U6-E1)") (class "Default")
      (node (ref "R27") (pin "2") (pinfunction "2_2") (pintype "passive"))
      (node (ref "U6") (pin "6") (pinfunction "E1_6") (pintype "passive"))
    )
    (net (code "26") (name "Net-(U6-E2)") (class "Default")
      (node (ref "R28") (pin "2") (pinfunction "2_2") (pintype "passive"))
      (node (ref "U6") (pin "4") (pinfunction "E2_4") (pintype "passive"))
    )
    (net (code "27") (name "Net-(U7-NFB)") (class "Default")
      (node (ref "C16") (pin "2") (pinfunction "2_2") (pintype "passive"))
      (node (ref "R29") (pin "1") (pinfunction "1_1") (pintype "passive"))
      (node (ref "R30") (pin "2") (pinfunction "2_2") (pintype "passive"))
      (node (ref "U7") (pin "3") (pinfunction "NFB_3") (pintype "input"))
    )
    (net (code "28") (name "Net-(U7-SW)") (class "Default")
      (node (ref "C15") (pin "1") (pinfunction "1_1") (pintype "passive"))
      (node (ref "L1") (pin "2") (pinfunction "2_2") (pintype "passive"))
      (node (ref "U7") (pin "1") (pinfunction "SW_1") (pintype "power_in"))
    )
    (net (code "29") (name "Net-(U8-SET)") (class "Default")
      (node (ref "C21") (pin "1") (pinfunction "1_1") (pintype "passive"))
      (node (ref "R32") (pin "1") (pinfunction "1_1") (pintype "passive"))
      (node (ref "U8") (pin "8") (pinfunction "SET_8") (pintype "passive"))
    )
    (net (code "30") (name "Net-(U10-TRIM{slash}NR)") (class "Default")
      (node (ref "C7") (pin "1") (pinfunction "1_1") (pintype "passive"))
      (node (ref "U10") (pin "5") (pinfunction "TRIM/NR_5") (pintype "passive"))
    )
    (net (code "31") (name "unconnected-(U3-PG-Pad5)") (class "Default")
      (node (ref "U3") (pin "5") (pinfunction "PG_5") (pintype "passive+no_connect"))
    )
    (net (code "32") (name "unconnected-(U8-PG-Pad4)") (class "Default")
      (node (ref "U8") (pin "4") (pinfunction "PG_4") (pintype "passive+no_connect"))
    )
    (net (code "33") (name "unconnected-(U8-VIOC-Pad7)") (class "Default")
      (node (ref "U8") (pin "7") (pinfunction "VIOC_7") (pintype "passive+no_connect"))
    )
    (net (code "34") (name "unconnected-(U10-DNC-Pad1)") (class "Default")
      (node (ref "U10") (pin "1") (pinfunction "DNC_1") (pintype "passive+no_connect"))
    )
    (net (code "35") (name "unconnected-(U10-DNC-Pad8)") (class "Default")
      (node (ref "U10") (pin "8") (pinfunction "DNC_8") (pintype "passive"))
    )
    (net (code "36") (name "unconnected-(U10-NC-Pad7)") (class "Default")
      (node (ref "U10") (pin "7") (pinfunction "NC_7") (pintype "passive+no_connect"))
    )
    (net (code "37") (name "unconnected-(U10-TEMP-Pad3)") (class "Default")
      (node (ref "U10") (pin "3") (pinfunction "TEMP_3") (pintype "passive"))
    )
  )
)
